# LED.net
KiCad netlist of a schematic drawn in EAGLE
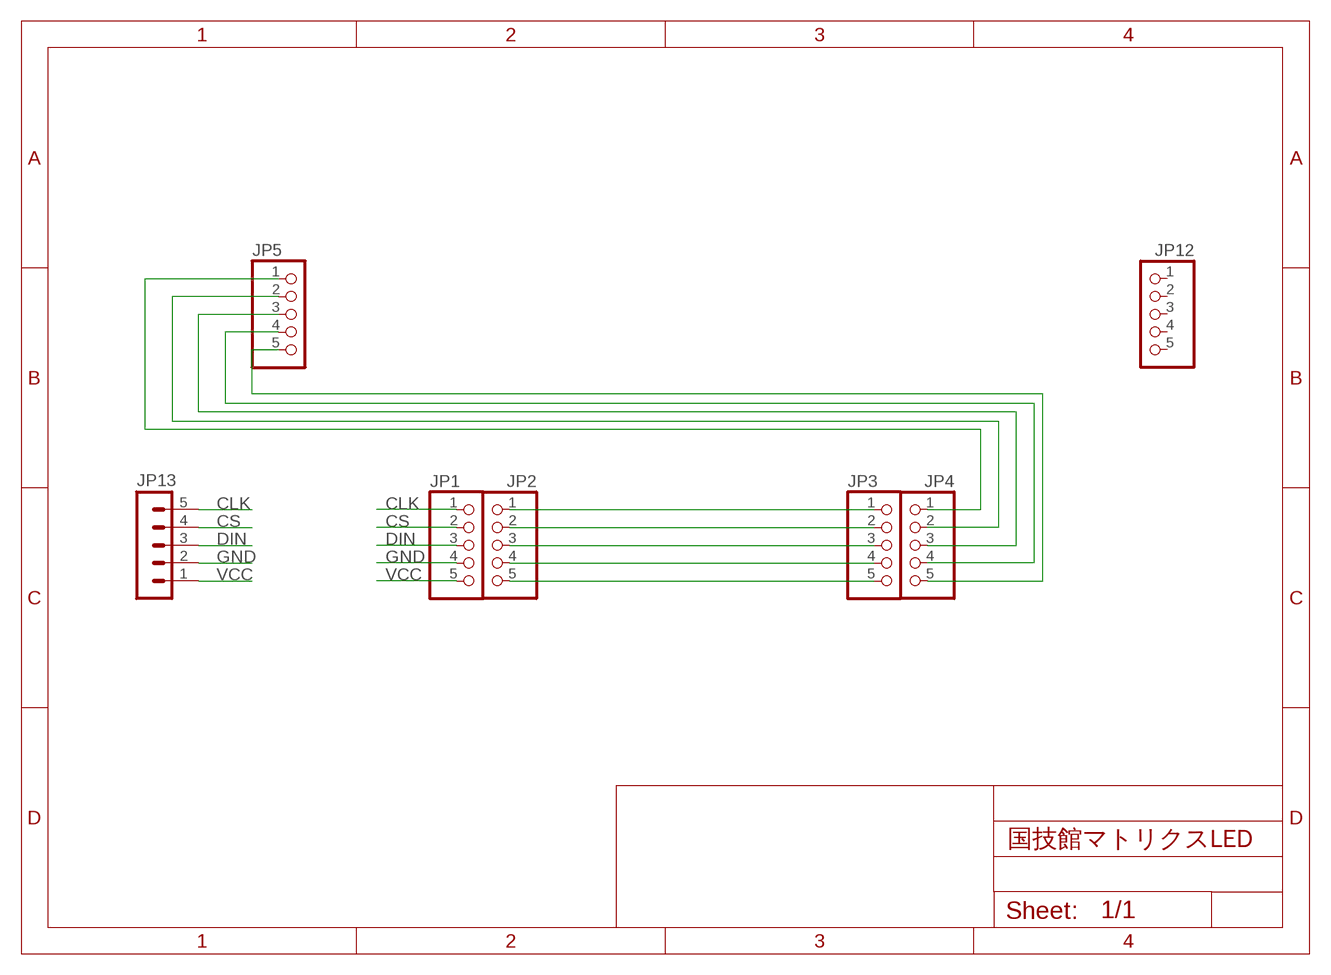
[diagram p0: schematic, sheet 1]

(export (version "E")
  (design (tool "Eeschema 10.0.6"))
  (components
    (comp (ref "JP1")
      (value "PINHD-1X5")
      (footprint "eagle-import:1X05")
      (libsource (lib "eagle-import") (part "PINHD-1X5"))
    )
    (comp (ref "JP2")
      (value "PINHD-1X5")
      (footprint "eagle-import:1X05")
      (libsource (lib "eagle-import") (part "PINHD-1X5"))
    )
    (comp (ref "JP3")
      (value "PINHD-1X5")
      (footprint "eagle-import:1X05")
      (libsource (lib "eagle-import") (part "PINHD-1X5"))
    )
    (comp (ref "JP4")
      (value "PINHD-1X5")
      (footprint "eagle-import:1X05")
      (libsource (lib "eagle-import") (part "PINHD-1X5"))
    )
    (comp (ref "JP5")
      (value "PINHD-1X5")
      (footprint "eagle-import:1X05")
      (libsource (lib "eagle-import") (part "PINHD-1X5"))
    )
    (comp (ref "JP12")
      (value "PINHD-1X5")
      (footprint "eagle-import:1X05")
      (libsource (lib "eagle-import") (part "PINHD-1X5"))
    )
    (comp (ref "JP13")
      (value "05-JST")
      (footprint "eagle-import:B5B-XH")
      (libsource (lib "eagle-import") (part "05-JST"))
    )
  )
  (nets
    (net (code "1") (name "/CLK") (class "Default")
      (node (ref "JP1") (pin "1") (pinfunction "1_1") (pintype "passive"))
      (node (ref "JP13") (pin "5") (pinfunction "5_5") (pintype "passive"))
    )
    (net (code "2") (name "/CS") (class "Default")
      (node (ref "JP1") (pin "2") (pinfunction "2_2") (pintype "passive"))
      (node (ref "JP13") (pin "4") (pinfunction "4_4") (pintype "passive"))
    )
    (net (code "3") (name "/DIN") (class "Default")
      (node (ref "JP1") (pin "3") (pinfunction "3_3") (pintype "passive"))
      (node (ref "JP13") (pin "3") (pinfunction "3_3") (pintype "passive"))
    )
    (net (code "4") (name "/GND") (class "Default")
      (node (ref "JP1") (pin "4") (pinfunction "4_4") (pintype "passive"))
      (node (ref "JP13") (pin "2") (pinfunction "2_2") (pintype "passive"))
    )
    (net (code "5") (name "/VCC") (class "Default")
      (node (ref "JP1") (pin "5") (pinfunction "5_5") (pintype "passive"))
      (node (ref "JP13") (pin "1") (pinfunction "1_1") (pintype "passive"))
    )
    (net (code "6") (name "Net-(JP2-Pad1)") (class "Default")
      (node (ref "JP2") (pin "1") (pinfunction "1_1") (pintype "passive"))
      (node (ref "JP3") (pin "1") (pinfunction "1_1") (pintype "passive"))
    )
    (net (code "7") (name "Net-(JP2-Pad2)") (class "Default")
      (node (ref "JP2") (pin "2") (pinfunction "2_2") (pintype "passive"))
      (node (ref "JP3") (pin "2") (pinfunction "2_2") (pintype "passive"))
    )
    (net (code "8") (name "Net-(JP2-Pad3)") (class "Default")
      (node (ref "JP2") (pin "3") (pinfunction "3_3") (pintype "passive"))
      (node (ref "JP3") (pin "3") (pinfunction "3_3") (pintype "passive"))
    )
    (net (code "9") (name "Net-(JP2-Pad4)") (class "Default")
      (node (ref "JP2") (pin "4") (pinfunction "4_4") (pintype "passive"))
      (node (ref "JP3") (pin "4") (pinfunction "4_4") (pintype "passive"))
    )
    (net (code "10") (name "Net-(JP2-Pad5)") (class "Default")
      (node (ref "JP2") (pin "5") (pinfunction "5_5") (pintype "passive"))
      (node (ref "JP3") (pin "5") (pinfunction "5_5") (pintype "passive"))
    )
    (net (code "11") (name "Net-(JP4-Pad1)") (class "Default")
      (node (ref "JP4") (pin "1") (pinfunction "1_1") (pintype "passive"))
      (node (ref "JP5") (pin "1") (pinfunction "1_1") (pintype "passive"))
    )
    (net (code "12") (name "Net-(JP4-Pad2)") (class "Default")
      (node (ref "JP4") (pin "2") (pinfunction "2_2") (pintype "passive"))
      (node (ref "JP5") (pin "2") (pinfunction "2_2") (pintype "passive"))
    )
    (net (code "13") (name "Net-(JP4-Pad3)") (class "Default")
      (node (ref "JP4") (pin "3") (pinfunction "3_3") (pintype "passive"))
      (node (ref "JP5") (pin "3") (pinfunction "3_3") (pintype "passive"))
    )
    (net (code "14") (name "Net-(JP4-Pad4)") (class "Default")
      (node (ref "JP4") (pin "4") (pinfunction "4_4") (pintype "passive"))
      (node (ref "JP5") (pin "4") (pinfunction "4_4") (pintype "passive"))
    )
    (net (code "15") (name "Net-(JP4-Pad5)") (class "Default")
      (node (ref "JP4") (pin "5") (pinfunction "5_5") (pintype "passive"))
      (node (ref "JP5") (pin "5") (pinfunction "5_5") (pintype "passive"))
    )
    (net (code "16") (name "unconnected-(JP12-Pad1)") (class "Default")
      (node (ref "JP12") (pin "1") (pinfunction "1_1") (pintype "passive"))
    )
    (net (code "17") (name "unconnected-(JP12-Pad2)") (class "Default")
      (node (ref "JP12") (pin "2") (pinfunction "2_2") (pintype "passive"))
    )
    (net (code "18") (name "unconnected-(JP12-Pad3)") (class "Default")
      (node (ref "JP12") (pin "3") (pinfunction "3_3") (pintype "passive"))
    )
    (net (code "19") (name "unconnected-(JP12-Pad4)") (class "Default")
      (node (ref "JP12") (pin "4") (pinfunction "4_4") (pintype "passive"))
    )
    (net (code "20") (name "unconnected-(JP12-Pad5)") (class "Default")
      (node (ref "JP12") (pin "5") (pinfunction "5_5") (pintype "passive"))
    )
  )
)
